# MT_MD_Converter.net
KiCad netlist of a schematic drawn in Altium Designer
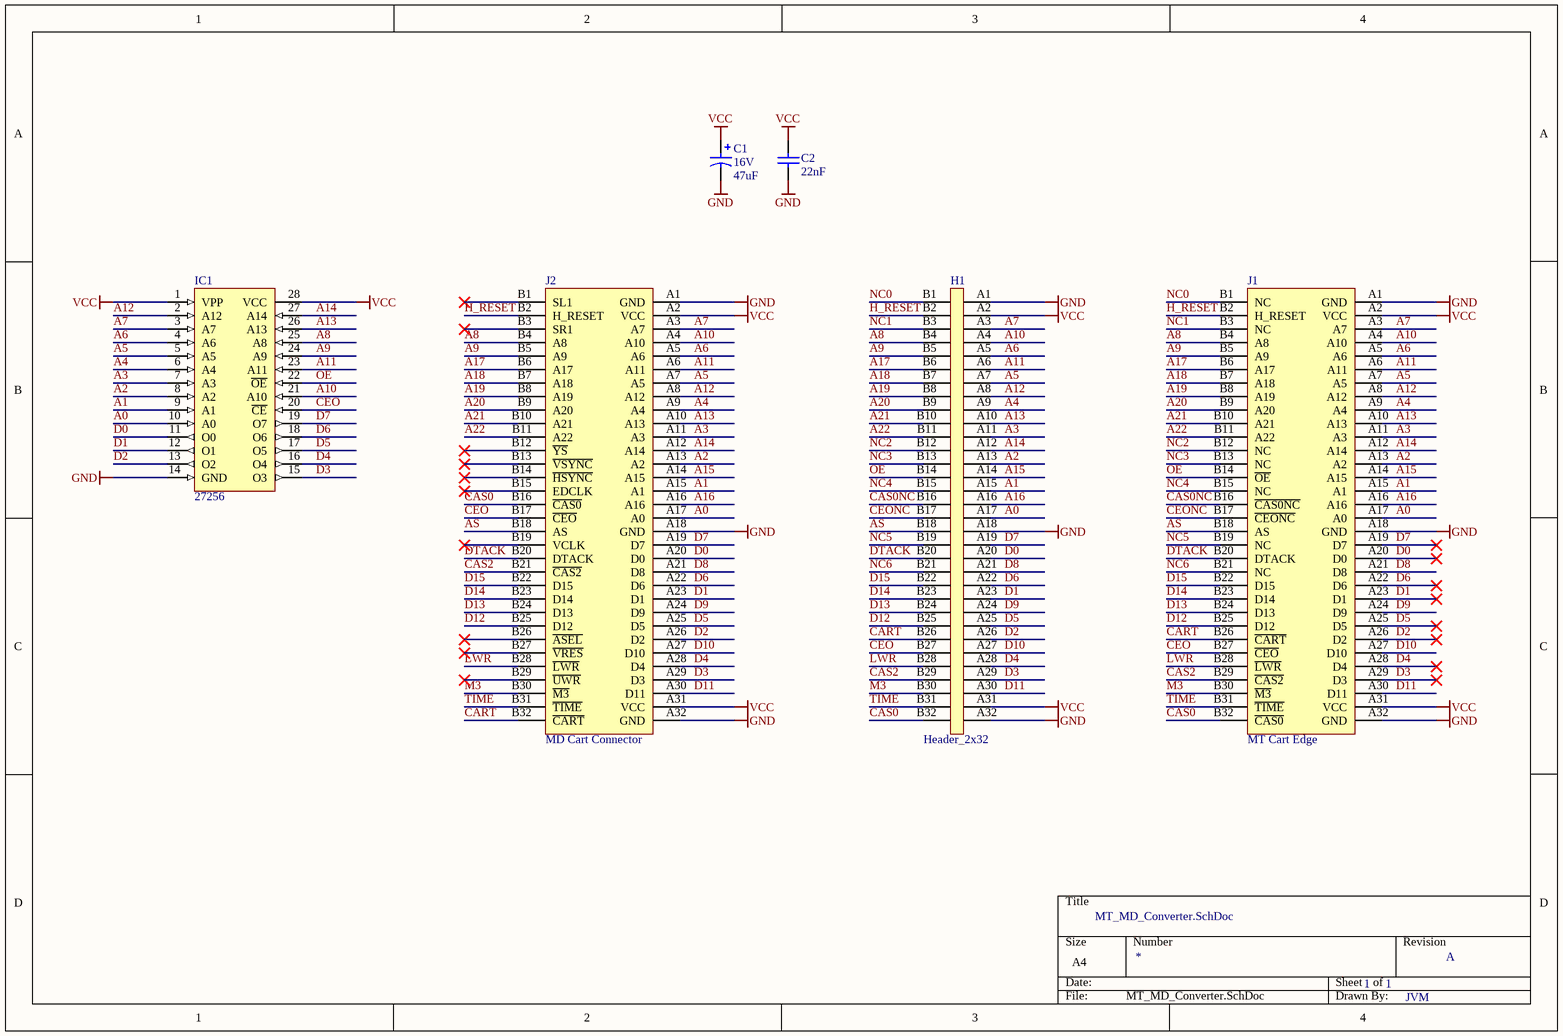
[diagram p0: MT_MD_Converter.SchDoc]

(export (version "E")
  (design (tool "Eeschema 10.0.6"))
  (components
    (comp (ref "C1")
      (value "47uF")
      (footprint "CapPol Mirror")
      (description "Polarized Capacitor, 2.54mm Pitch, 5mm Width, mirrored")
      (fields (field (name "VOLTAGE") "16V") (field (name "Comment") "Cap2.54P5.0D"))
      (libsource (lib "171-5782") (part "Cap2.54P5.0D_mirror"))
    )
    (comp (ref "C2")
      (value "22nF")
      (footprint "CapCer")
      (description "Capacitor (THT), Ceramic, 5.08mm Pitch")
      (fields (field (name "Comment") "CapCer"))
      (libsource (lib "171-5782") (part "CapCer"))
    )
    (comp (ref "H1")
      (value "Header_2x32")
      (footprint "Header_2x32")
      (libsource (lib "171-5782") (part "Header_2x32"))
    )
    (comp (ref "IC1")
      (value "27256")
      (footprint "27256")
      (description "256K EPROM")
      (libsource (lib "171-5782") (part "27256"))
    )
    (comp (ref "J1")
      (value "MT Cart Edge")
      (footprint "MT_Cart_Edge")
      (libsource (lib "171-5782") (part "MT_CART_EDGE_CON"))
    )
    (comp (ref "J2")
      (value "MD Cart Connector")
      (footprint "MD_Cart_CON")
      (libsource (lib "171-5782") (part "MD_CART_CON"))
    )
  )
  (nets
    (net (code "1") (name "/A0") (class "Default")
      (node (ref "H1") (pin "A17") (pintype "passive"))
      (node (ref "IC1") (pin "10") (pinfunction "A0_10") (pintype "input"))
      (node (ref "J1") (pin "A17") (pinfunction "A0_A17") (pintype "passive"))
      (node (ref "J2") (pin "A17") (pinfunction "A0_A17") (pintype "passive"))
    )
    (net (code "2") (name "/A1") (class "Default")
      (node (ref "H1") (pin "A15") (pintype "passive"))
      (node (ref "IC1") (pin "9") (pinfunction "A1_9") (pintype "input"))
      (node (ref "J1") (pin "A15") (pinfunction "A1_A15") (pintype "passive"))
      (node (ref "J2") (pin "A15") (pinfunction "A1_A15") (pintype "passive"))
    )
    (net (code "3") (name "/A2") (class "Default")
      (node (ref "H1") (pin "A13") (pintype "passive"))
      (node (ref "IC1") (pin "8") (pinfunction "A2_8") (pintype "input"))
      (node (ref "J1") (pin "A13") (pinfunction "A2_A13") (pintype "passive"))
      (node (ref "J2") (pin "A13") (pinfunction "A2_A13") (pintype "passive"))
    )
    (net (code "4") (name "/A3") (class "Default")
      (node (ref "H1") (pin "A11") (pintype "passive"))
      (node (ref "IC1") (pin "7") (pinfunction "A3_7") (pintype "input"))
      (node (ref "J1") (pin "A11") (pinfunction "A3_A11") (pintype "passive"))
      (node (ref "J2") (pin "A11") (pinfunction "A3_A11") (pintype "passive"))
    )
    (net (code "5") (name "/A4") (class "Default")
      (node (ref "H1") (pin "A9") (pintype "passive"))
      (node (ref "IC1") (pin "6") (pinfunction "A4_6") (pintype "input"))
      (node (ref "J1") (pin "A9") (pinfunction "A4_A9") (pintype "passive"))
      (node (ref "J2") (pin "A9") (pinfunction "A4_A9") (pintype "passive"))
    )
    (net (code "6") (name "/A5") (class "Default")
      (node (ref "H1") (pin "A7") (pintype "passive"))
      (node (ref "IC1") (pin "5") (pinfunction "A5_5") (pintype "input"))
      (node (ref "J1") (pin "A7") (pinfunction "A5_A7") (pintype "passive"))
      (node (ref "J2") (pin "A7") (pinfunction "A5_A7") (pintype "passive"))
    )
    (net (code "7") (name "/A6") (class "Default")
      (node (ref "H1") (pin "A5") (pintype "passive"))
      (node (ref "IC1") (pin "4") (pinfunction "A6_4") (pintype "input"))
      (node (ref "J1") (pin "A5") (pinfunction "A6_A5") (pintype "passive"))
      (node (ref "J2") (pin "A5") (pinfunction "A6_A5") (pintype "passive"))
    )
    (net (code "8") (name "/A7") (class "Default")
      (node (ref "H1") (pin "A3") (pintype "passive"))
      (node (ref "IC1") (pin "3") (pinfunction "A7_3") (pintype "input"))
      (node (ref "J1") (pin "A3") (pinfunction "A7_A3") (pintype "passive"))
      (node (ref "J2") (pin "A3") (pinfunction "A7_A3") (pintype "passive"))
    )
    (net (code "9") (name "/A8") (class "Default")
      (node (ref "H1") (pin "B4") (pintype "passive"))
      (node (ref "IC1") (pin "25") (pinfunction "A8_25") (pintype "input"))
      (node (ref "J1") (pin "B4") (pinfunction "A8_B4") (pintype "passive"))
      (node (ref "J2") (pin "B4") (pinfunction "A8_B4") (pintype "passive"))
    )
    (net (code "10") (name "/A9") (class "Default")
      (node (ref "H1") (pin "B5") (pintype "passive"))
      (node (ref "IC1") (pin "24") (pinfunction "A9_24") (pintype "input"))
      (node (ref "J1") (pin "B5") (pinfunction "A9_B5") (pintype "passive"))
      (node (ref "J2") (pin "B5") (pinfunction "A9_B5") (pintype "passive"))
    )
    (net (code "11") (name "/A10") (class "Default")
      (node (ref "H1") (pin "A4") (pintype "passive"))
      (node (ref "IC1") (pin "21") (pinfunction "A10_21") (pintype "input"))
      (node (ref "J1") (pin "A4") (pinfunction "A10_A4") (pintype "passive"))
      (node (ref "J2") (pin "A4") (pinfunction "A10_A4") (pintype "passive"))
    )
    (net (code "12") (name "/A11") (class "Default")
      (node (ref "H1") (pin "A6") (pintype "passive"))
      (node (ref "IC1") (pin "23") (pinfunction "A11_23") (pintype "input"))
      (node (ref "J1") (pin "A6") (pinfunction "A11_A6") (pintype "passive"))
      (node (ref "J2") (pin "A6") (pinfunction "A11_A6") (pintype "passive"))
    )
    (net (code "13") (name "/A12") (class "Default")
      (node (ref "H1") (pin "A8") (pintype "passive"))
      (node (ref "IC1") (pin "2") (pinfunction "A12_2") (pintype "input"))
      (node (ref "J1") (pin "A8") (pinfunction "A12_A8") (pintype "passive"))
      (node (ref "J2") (pin "A8") (pinfunction "A12_A8") (pintype "passive"))
    )
    (net (code "14") (name "/A13") (class "Default")
      (node (ref "H1") (pin "A10") (pintype "passive"))
      (node (ref "IC1") (pin "26") (pinfunction "A13_26") (pintype "input"))
      (node (ref "J1") (pin "A10") (pinfunction "A13_A10") (pintype "passive"))
      (node (ref "J2") (pin "A10") (pinfunction "A13_A10") (pintype "passive"))
    )
    (net (code "15") (name "/A14") (class "Default")
      (node (ref "H1") (pin "A12") (pintype "passive"))
      (node (ref "IC1") (pin "27") (pinfunction "A14_27") (pintype "input"))
      (node (ref "J1") (pin "A12") (pinfunction "A14_A12") (pintype "passive"))
      (node (ref "J2") (pin "A12") (pinfunction "A14_A12") (pintype "passive"))
    )
    (net (code "16") (name "/A15") (class "Default")
      (node (ref "H1") (pin "A14") (pintype "passive"))
      (node (ref "J1") (pin "A14") (pinfunction "A15_A14") (pintype "passive"))
      (node (ref "J2") (pin "A14") (pinfunction "A15_A14") (pintype "passive"))
    )
    (net (code "17") (name "/A16") (class "Default")
      (node (ref "H1") (pin "A16") (pintype "passive"))
      (node (ref "J1") (pin "A16") (pinfunction "A16_A16") (pintype "passive"))
      (node (ref "J2") (pin "A16") (pinfunction "A16_A16") (pintype "passive"))
    )
    (net (code "18") (name "/A17") (class "Default")
      (node (ref "H1") (pin "B6") (pintype "passive"))
      (node (ref "J1") (pin "B6") (pinfunction "A17_B6") (pintype "passive"))
      (node (ref "J2") (pin "B6") (pinfunction "A17_B6") (pintype "passive"))
    )
    (net (code "19") (name "/A18") (class "Default")
      (node (ref "H1") (pin "B7") (pintype "passive"))
      (node (ref "J1") (pin "B7") (pinfunction "A18_B7") (pintype "passive"))
      (node (ref "J2") (pin "B7") (pinfunction "A18_B7") (pintype "passive"))
    )
    (net (code "20") (name "/A19") (class "Default")
      (node (ref "H1") (pin "B8") (pintype "passive"))
      (node (ref "J1") (pin "B8") (pinfunction "A19_B8") (pintype "passive"))
      (node (ref "J2") (pin "B8") (pinfunction "A19_B8") (pintype "passive"))
    )
    (net (code "21") (name "/A20") (class "Default")
      (node (ref "H1") (pin "B9") (pintype "passive"))
      (node (ref "J1") (pin "B9") (pinfunction "A20_B9") (pintype "passive"))
      (node (ref "J2") (pin "B9") (pinfunction "A20_B9") (pintype "passive"))
    )
    (net (code "22") (name "/A21") (class "Default")
      (node (ref "H1") (pin "B10") (pintype "passive"))
      (node (ref "J1") (pin "B10") (pinfunction "A21_B10") (pintype "passive"))
      (node (ref "J2") (pin "B10") (pinfunction "A21_B10") (pintype "passive"))
    )
    (net (code "23") (name "/A22") (class "Default")
      (node (ref "H1") (pin "B11") (pintype "passive"))
      (node (ref "J1") (pin "B11") (pinfunction "A22_B11") (pintype "passive"))
      (node (ref "J2") (pin "B11") (pinfunction "A22_B11") (pintype "passive"))
    )
    (net (code "24") (name "/AS") (class "Default")
      (node (ref "H1") (pin "B18") (pintype "passive"))
      (node (ref "J1") (pin "B18") (pinfunction "AS_B18") (pintype "passive"))
      (node (ref "J2") (pin "B18") (pinfunction "AS_B18") (pintype "passive"))
    )
    (net (code "25") (name "/CART") (class "Default")
      (node (ref "H1") (pin "B26") (pintype "passive"))
      (node (ref "J1") (pin "B26") (pinfunction "~{CART}_B26") (pintype "passive"))
      (node (ref "J2") (pin "B32") (pinfunction "~{CART}_B32") (pintype "passive"))
    )
    (net (code "26") (name "/CAS0") (class "Default")
      (node (ref "H1") (pin "B32") (pintype "passive"))
      (node (ref "J1") (pin "B32") (pinfunction "~{CAS0}_B32") (pintype "passive"))
      (node (ref "J2") (pin "B16") (pinfunction "~{CAS0}_B16") (pintype "passive"))
    )
    (net (code "27") (name "/CAS0NC") (class "Default")
      (node (ref "H1") (pin "B16") (pintype "passive"))
      (node (ref "J1") (pin "B16") (pinfunction "~{CAS0NC}_B16") (pintype "passive"))
    )
    (net (code "28") (name "/CAS2") (class "Default")
      (node (ref "H1") (pin "B29") (pintype "passive"))
      (node (ref "J1") (pin "B29") (pinfunction "~{CAS2}_B29") (pintype "passive"))
      (node (ref "J2") (pin "B21") (pinfunction "~{CAS2}_B21") (pintype "passive"))
    )
    (net (code "29") (name "/CEO") (class "Default")
      (node (ref "H1") (pin "B27") (pintype "passive"))
      (node (ref "IC1") (pin "20") (pinfunction "~{CE}_20") (pintype "input"))
      (node (ref "J1") (pin "B27") (pinfunction "~{CEO}_B27") (pintype "passive"))
      (node (ref "J2") (pin "B17") (pinfunction "~{CEO}_B17") (pintype "passive"))
    )
    (net (code "30") (name "/CEONC") (class "Default")
      (node (ref "H1") (pin "B17") (pintype "passive"))
      (node (ref "J1") (pin "B17") (pinfunction "~{CEONC}_B17") (pintype "passive"))
    )
    (net (code "31") (name "/D0") (class "Default")
      (node (ref "H1") (pin "A20") (pintype "passive"))
      (node (ref "IC1") (pin "11") (pinfunction "O0_11") (pintype "output"))
      (node (ref "J1") (pin "A20") (pinfunction "D0_A20") (pintype "passive"))
      (node (ref "J2") (pin "A20") (pinfunction "D0_A20") (pintype "passive"))
    )
    (net (code "32") (name "/D1") (class "Default")
      (node (ref "H1") (pin "A23") (pintype "passive"))
      (node (ref "IC1") (pin "12") (pinfunction "O1_12") (pintype "output"))
      (node (ref "J1") (pin "A23") (pinfunction "D1_A23") (pintype "passive"))
      (node (ref "J2") (pin "A23") (pinfunction "D1_A23") (pintype "passive"))
    )
    (net (code "33") (name "/D2") (class "Default")
      (node (ref "H1") (pin "A26") (pintype "passive"))
      (node (ref "IC1") (pin "13") (pinfunction "O2_13") (pintype "output"))
      (node (ref "J1") (pin "A26") (pinfunction "D2_A26") (pintype "passive"))
      (node (ref "J2") (pin "A26") (pinfunction "D2_A26") (pintype "passive"))
    )
    (net (code "34") (name "/D3") (class "Default")
      (node (ref "H1") (pin "A29") (pintype "passive"))
      (node (ref "IC1") (pin "15") (pinfunction "O3_15") (pintype "output"))
      (node (ref "J1") (pin "A29") (pinfunction "D3_A29") (pintype "passive"))
      (node (ref "J2") (pin "A29") (pinfunction "D3_A29") (pintype "passive"))
    )
    (net (code "35") (name "/D4") (class "Default")
      (node (ref "H1") (pin "A28") (pintype "passive"))
      (node (ref "IC1") (pin "16") (pinfunction "O4_16") (pintype "output"))
      (node (ref "J1") (pin "A28") (pinfunction "D4_A28") (pintype "passive"))
      (node (ref "J2") (pin "A28") (pinfunction "D4_A28") (pintype "passive"))
    )
    (net (code "36") (name "/D5") (class "Default")
      (node (ref "H1") (pin "A25") (pintype "passive"))
      (node (ref "IC1") (pin "17") (pinfunction "O5_17") (pintype "output"))
      (node (ref "J1") (pin "A25") (pinfunction "D5_A25") (pintype "passive"))
      (node (ref "J2") (pin "A25") (pinfunction "D5_A25") (pintype "passive"))
    )
    (net (code "37") (name "/D6") (class "Default")
      (node (ref "H1") (pin "A22") (pintype "passive"))
      (node (ref "IC1") (pin "18") (pinfunction "O6_18") (pintype "output"))
      (node (ref "J1") (pin "A22") (pinfunction "D6_A22") (pintype "passive"))
      (node (ref "J2") (pin "A22") (pinfunction "D6_A22") (pintype "passive"))
    )
    (net (code "38") (name "/D7") (class "Default")
      (node (ref "H1") (pin "A19") (pintype "passive"))
      (node (ref "IC1") (pin "19") (pinfunction "O7_19") (pintype "output"))
      (node (ref "J1") (pin "A19") (pinfunction "D7_A19") (pintype "passive"))
      (node (ref "J2") (pin "A19") (pinfunction "D7_A19") (pintype "passive"))
    )
    (net (code "39") (name "/D8") (class "Default")
      (node (ref "H1") (pin "A21") (pintype "passive"))
      (node (ref "J1") (pin "A21") (pinfunction "D8_A21") (pintype "passive"))
      (node (ref "J2") (pin "A21") (pinfunction "D8_A21") (pintype "passive"))
    )
    (net (code "40") (name "/D9") (class "Default")
      (node (ref "H1") (pin "A24") (pintype "passive"))
      (node (ref "J1") (pin "A24") (pinfunction "D9_A24") (pintype "passive"))
      (node (ref "J2") (pin "A24") (pinfunction "D9_A24") (pintype "passive"))
    )
    (net (code "41") (name "/D10") (class "Default")
      (node (ref "H1") (pin "A27") (pintype "passive"))
      (node (ref "J1") (pin "A27") (pinfunction "D10_A27") (pintype "passive"))
      (node (ref "J2") (pin "A27") (pinfunction "D10_A27") (pintype "passive"))
    )
    (net (code "42") (name "/D11") (class "Default")
      (node (ref "H1") (pin "A30") (pintype "passive"))
      (node (ref "J1") (pin "A30") (pinfunction "D11_A30") (pintype "passive"))
      (node (ref "J2") (pin "A30") (pinfunction "D11_A30") (pintype "passive"))
    )
    (net (code "43") (name "/D12") (class "Default")
      (node (ref "H1") (pin "B25") (pintype "passive"))
      (node (ref "J1") (pin "B25") (pinfunction "D12_B25") (pintype "passive"))
      (node (ref "J2") (pin "B25") (pinfunction "D12_B25") (pintype "passive"))
    )
    (net (code "44") (name "/D13") (class "Default")
      (node (ref "H1") (pin "B24") (pintype "passive"))
      (node (ref "J1") (pin "B24") (pinfunction "D13_B24") (pintype "passive"))
      (node (ref "J2") (pin "B24") (pinfunction "D13_B24") (pintype "passive"))
    )
    (net (code "45") (name "/D14") (class "Default")
      (node (ref "H1") (pin "B23") (pintype "passive"))
      (node (ref "J1") (pin "B23") (pinfunction "D14_B23") (pintype "passive"))
      (node (ref "J2") (pin "B23") (pinfunction "D14_B23") (pintype "passive"))
    )
    (net (code "46") (name "/D15") (class "Default")
      (node (ref "H1") (pin "B22") (pintype "passive"))
      (node (ref "J1") (pin "B22") (pinfunction "D15_B22") (pintype "passive"))
      (node (ref "J2") (pin "B22") (pinfunction "D15_B22") (pintype "passive"))
    )
    (net (code "47") (name "/DTACK") (class "Default")
      (node (ref "H1") (pin "B20") (pintype "passive"))
      (node (ref "J1") (pin "B20") (pinfunction "DTACK_B20") (pintype "passive"))
      (node (ref "J2") (pin "B20") (pinfunction "DTACK_B20") (pintype "passive"))
    )
    (net (code "48") (name "/H_RESET") (class "Default")
      (node (ref "H1") (pin "B2") (pintype "passive"))
      (node (ref "J1") (pin "B2") (pinfunction "H_RESET_B2") (pintype "passive"))
      (node (ref "J2") (pin "B2") (pinfunction "H_RESET_B2") (pintype "passive"))
    )
    (net (code "49") (name "/LWR") (class "Default")
      (node (ref "H1") (pin "B28") (pintype "passive"))
      (node (ref "J1") (pin "B28") (pinfunction "~{LWR}_B28") (pintype "passive"))
      (node (ref "J2") (pin "B28") (pinfunction "~{LWR}_B28") (pintype "passive"))
    )
    (net (code "50") (name "/M3") (class "Default")
      (node (ref "H1") (pin "B30") (pintype "passive"))
      (node (ref "J1") (pin "B30") (pinfunction "~{M3}_B30") (pintype "passive"))
      (node (ref "J2") (pin "B30") (pinfunction "~{M3}_B30") (pintype "passive"))
    )
    (net (code "51") (name "/NC0") (class "Default")
      (node (ref "H1") (pin "B1") (pintype "passive"))
      (node (ref "J1") (pin "B1") (pinfunction "NC_B1") (pintype "passive"))
    )
    (net (code "52") (name "/NC1") (class "Default")
      (node (ref "H1") (pin "B3") (pintype "passive"))
      (node (ref "J1") (pin "B3") (pinfunction "NC_B3") (pintype "passive"))
    )
    (net (code "53") (name "/NC2") (class "Default")
      (node (ref "H1") (pin "B12") (pintype "passive"))
      (node (ref "J1") (pin "B12") (pinfunction "NC_B12") (pintype "passive"))
    )
    (net (code "54") (name "/NC3") (class "Default")
      (node (ref "H1") (pin "B13") (pintype "passive"))
      (node (ref "J1") (pin "B13") (pinfunction "NC_B13") (pintype "passive"))
    )
    (net (code "55") (name "/NC4") (class "Default")
      (node (ref "H1") (pin "B15") (pintype "passive"))
      (node (ref "J1") (pin "B15") (pinfunction "NC_B15") (pintype "passive"))
    )
    (net (code "56") (name "/NC5") (class "Default")
      (node (ref "H1") (pin "B19") (pintype "passive"))
      (node (ref "J1") (pin "B19") (pinfunction "NC_B19") (pintype "passive"))
    )
    (net (code "57") (name "/NC6") (class "Default")
      (node (ref "H1") (pin "B21") (pintype "passive"))
      (node (ref "J1") (pin "B21") (pinfunction "NC_B21") (pintype "passive"))
    )
    (net (code "58") (name "/OE") (class "Default")
      (node (ref "H1") (pin "B14") (pintype "passive"))
      (node (ref "IC1") (pin "22") (pinfunction "~{OE}_22") (pintype "input"))
      (node (ref "J1") (pin "B14") (pinfunction "~{OE}_B14") (pintype "passive"))
    )
    (net (code "59") (name "/TIME") (class "Default")
      (node (ref "H1") (pin "B31") (pintype "passive"))
      (node (ref "J1") (pin "B31") (pinfunction "~{TIME}_B31") (pintype "passive"))
      (node (ref "J2") (pin "B31") (pinfunction "~{TIME}_B31") (pintype "passive"))
    )
    (net (code "60") (name "GND") (class "Default")
      (node (ref "C1") (pin "2") (pinfunction "2_2") (pintype "passive"))
      (node (ref "C2") (pin "1") (pinfunction "1_1") (pintype "passive"))
      (node (ref "H1") (pin "A1") (pintype "passive"))
      (node (ref "H1") (pin "A18") (pintype "passive"))
      (node (ref "H1") (pin "A32") (pintype "passive"))
      (node (ref "IC1") (pin "14") (pinfunction "GND_14") (pintype "input"))
      (node (ref "J1") (pin "A1") (pinfunction "GND_A1") (pintype "passive"))
      (node (ref "J1") (pin "A18") (pinfunction "GND_A18") (pintype "passive"))
      (node (ref "J1") (pin "A32") (pinfunction "GND_A32") (pintype "passive"))
      (node (ref "J2") (pin "A1") (pinfunction "GND_A1") (pintype "passive"))
      (node (ref "J2") (pin "A18") (pinfunction "GND_A18") (pintype "passive"))
      (node (ref "J2") (pin "A32") (pinfunction "GND_A32") (pintype "passive"))
    )
    (net (code "61") (name "VCC") (class "Default")
      (node (ref "C1") (pin "1") (pinfunction "1_1") (pintype "passive"))
      (node (ref "C2") (pin "2") (pinfunction "2_2") (pintype "passive"))
      (node (ref "H1") (pin "A2") (pintype "passive"))
      (node (ref "H1") (pin "A31") (pintype "passive"))
      (node (ref "IC1") (pin "1") (pinfunction "VPP_1") (pintype "input"))
      (node (ref "IC1") (pin "28") (pinfunction "VCC_28") (pintype "power_in"))
      (node (ref "J1") (pin "A2") (pinfunction "VCC_A2") (pintype "passive"))
      (node (ref "J1") (pin "A31") (pinfunction "VCC_A31") (pintype "passive"))
      (node (ref "J2") (pin "A2") (pinfunction "VCC_A2") (pintype "passive"))
      (node (ref "J2") (pin "A31") (pinfunction "VCC_A31") (pintype "passive"))
    )
    (net (code "62") (name "unconnected-(J2-EDCLK-PadB15)") (class "Default")
      (node (ref "J2") (pin "B15") (pinfunction "EDCLK_B15") (pintype "passive+no_connect"))
    )
    (net (code "63") (name "unconnected-(J2-SL1-PadB1)") (class "Default")
      (node (ref "J2") (pin "B1") (pinfunction "SL1_B1") (pintype "passive+no_connect"))
    )
    (net (code "64") (name "unconnected-(J2-SR1-PadB3)") (class "Default")
      (node (ref "J2") (pin "B3") (pinfunction "SR1_B3") (pintype "passive+no_connect"))
    )
    (net (code "65") (name "unconnected-(J2-VCLK-PadB19)") (class "Default")
      (node (ref "J2") (pin "B19") (pinfunction "VCLK_B19") (pintype "passive+no_connect"))
    )
    (net (code "66") (name "unconnected-(J2-~{ASEL}-PadB26)") (class "Default")
      (node (ref "J2") (pin "B26") (pinfunction "~{ASEL}_B26") (pintype "passive+no_connect"))
    )
    (net (code "67") (name "unconnected-(J2-~{HSYNC}-PadB14)") (class "Default")
      (node (ref "J2") (pin "B14") (pinfunction "~{HSYNC}_B14") (pintype "passive+no_connect"))
    )
    (net (code "68") (name "unconnected-(J2-~{UWR}-PadB29)") (class "Default")
      (node (ref "J2") (pin "B29") (pinfunction "~{UWR}_B29") (pintype "passive+no_connect"))
    )
    (net (code "69") (name "unconnected-(J2-~{VRES}-PadB27)") (class "Default")
      (node (ref "J2") (pin "B27") (pinfunction "~{VRES}_B27") (pintype "passive+no_connect"))
    )
    (net (code "70") (name "unconnected-(J2-~{VSYNC}-PadB13)") (class "Default")
      (node (ref "J2") (pin "B13") (pinfunction "~{VSYNC}_B13") (pintype "passive+no_connect"))
    )
    (net (code "71") (name "unconnected-(J2-~{YS}-PadB12)") (class "Default")
      (node (ref "J2") (pin "B12") (pinfunction "~{YS}_B12") (pintype "passive+no_connect"))
    )
  )
)
